# SP.net
KiCad netlist of a schematic drawn in EAGLE
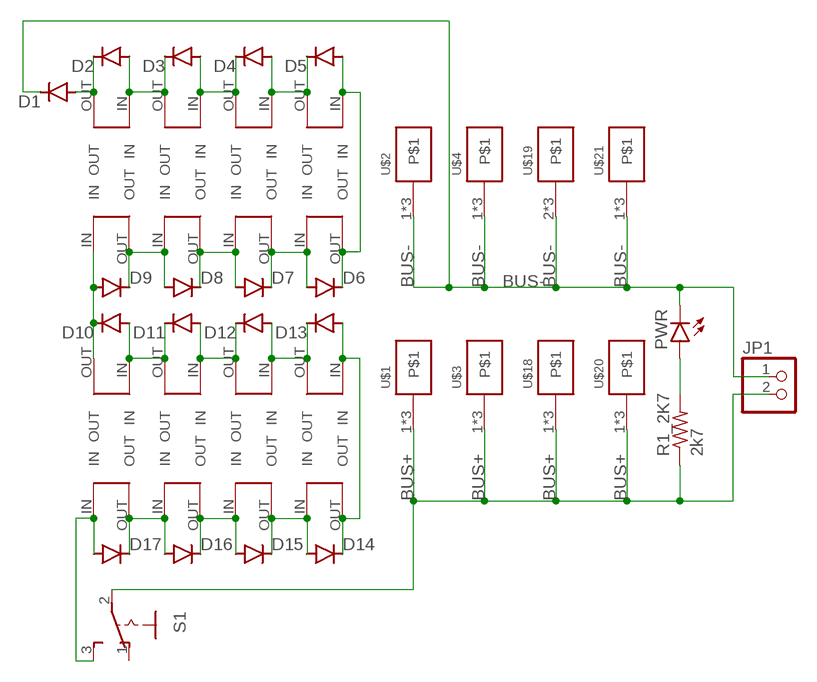
[diagram p0: schematic, sheet 1]

(export (version "E")
  (design (tool "Eeschema 10.0.6"))
  (components
    (comp (ref "D1")
      (value "MBR0520LT")
      (footprint "eagle-import:SOD123")
      (libsource (lib "eagle-import") (part "MBR0520LT"))
    )
    (comp (ref "D2")
      (value "MBR0520LT")
      (footprint "eagle-import:SOD123")
      (libsource (lib "eagle-import") (part "MBR0520LT"))
    )
    (comp (ref "D3")
      (value "MBR0520LT")
      (footprint "eagle-import:SOD123")
      (libsource (lib "eagle-import") (part "MBR0520LT"))
    )
    (comp (ref "D4")
      (value "MBR0520LT")
      (footprint "eagle-import:SOD123")
      (libsource (lib "eagle-import") (part "MBR0520LT"))
    )
    (comp (ref "D5")
      (value "MBR0520LT")
      (footprint "eagle-import:SOD123")
      (libsource (lib "eagle-import") (part "MBR0520LT"))
    )
    (comp (ref "D6")
      (value "MBR0520LT")
      (footprint "eagle-import:SOD123")
      (libsource (lib "eagle-import") (part "MBR0520LT"))
    )
    (comp (ref "D7")
      (value "MBR0520LT")
      (footprint "eagle-import:SOD123")
      (libsource (lib "eagle-import") (part "MBR0520LT"))
    )
    (comp (ref "D8")
      (value "MBR0520LT")
      (footprint "eagle-import:SOD123")
      (libsource (lib "eagle-import") (part "MBR0520LT"))
    )
    (comp (ref "D9")
      (value "MBR0520LT")
      (footprint "eagle-import:SOD123")
      (libsource (lib "eagle-import") (part "MBR0520LT"))
    )
    (comp (ref "D10")
      (value "MBR0520LT")
      (footprint "eagle-import:SOD123")
      (libsource (lib "eagle-import") (part "MBR0520LT"))
    )
    (comp (ref "D11")
      (value "MBR0520LT")
      (footprint "eagle-import:SOD123")
      (libsource (lib "eagle-import") (part "MBR0520LT"))
    )
    (comp (ref "D12")
      (value "MBR0520LT")
      (footprint "eagle-import:SOD123")
      (libsource (lib "eagle-import") (part "MBR0520LT"))
    )
    (comp (ref "D13")
      (value "MBR0520LT")
      (footprint "eagle-import:SOD123")
      (libsource (lib "eagle-import") (part "MBR0520LT"))
    )
    (comp (ref "D14")
      (value "MBR0520LT")
      (footprint "eagle-import:SOD123")
      (libsource (lib "eagle-import") (part "MBR0520LT"))
    )
    (comp (ref "D15")
      (value "MBR0520LT")
      (footprint "eagle-import:SOD123")
      (libsource (lib "eagle-import") (part "MBR0520LT"))
    )
    (comp (ref "D16")
      (value "MBR0520LT")
      (footprint "eagle-import:SOD123")
      (libsource (lib "eagle-import") (part "MBR0520LT"))
    )
    (comp (ref "D17")
      (value "MBR0520LT")
      (footprint "eagle-import:SOD123")
      (libsource (lib "eagle-import") (part "MBR0520LT"))
    )
    (comp (ref "JP1")
      (value "PINHD-1X2")
      (footprint "eagle-import:1X02")
      (libsource (lib "eagle-import") (part "PINHD-1X2"))
    )
    (comp (ref "PWR")
      (value "LEDCHIPLED_0603")
      (footprint "eagle-import:CHIPLED_0603")
      (libsource (lib "eagle-import") (part "LEDCHIPLED_0603"))
    )
    (comp (ref "R1_2K7")
      (value "2k7")
      (footprint "eagle-import:R0603")
      (libsource (lib "eagle-import") (part "R-US_R0603"))
    )
    (comp (ref "S1")
      (value "255SB")
      (footprint "eagle-import:255SB")
      (libsource (lib "eagle-import") (part "255SB"))
    )
    (comp (ref "SOL1")
      (value "SOLAR_0")
      (footprint "eagle-import:SOLAR_0")
      (libsource (lib "eagle-import") (part "SOLAR_0"))
    )
    (comp (ref "SOL2")
      (value "SOLAR_0")
      (footprint "eagle-import:SOLAR_0")
      (libsource (lib "eagle-import") (part "SOLAR_0"))
    )
    (comp (ref "SOL3")
      (value "SOLAR_0")
      (footprint "eagle-import:SOLAR_0")
      (libsource (lib "eagle-import") (part "SOLAR_0"))
    )
    (comp (ref "SOL4")
      (value "SOLAR_1")
      (footprint "eagle-import:SOLAR_1")
      (libsource (lib "eagle-import") (part "SOLAR_1"))
    )
    (comp (ref "SOL5")
      (value "SOLAR_0")
      (footprint "eagle-import:SOLAR_0")
      (libsource (lib "eagle-import") (part "SOLAR_0"))
    )
    (comp (ref "SOL6")
      (value "SOLAR_0")
      (footprint "eagle-import:SOLAR_0")
      (libsource (lib "eagle-import") (part "SOLAR_0"))
    )
    (comp (ref "SOL7")
      (value "SOLAR_0")
      (footprint "eagle-import:SOLAR_0")
      (libsource (lib "eagle-import") (part "SOLAR_0"))
    )
    (comp (ref "SOL8")
      (value "SOLAR_1")
      (footprint "eagle-import:SOLAR_1")
      (libsource (lib "eagle-import") (part "SOLAR_1"))
    )
    (comp (ref "SOL9")
      (value "SOLAR_0")
      (footprint "eagle-import:SOLAR_0")
      (libsource (lib "eagle-import") (part "SOLAR_0"))
    )
    (comp (ref "SOL10")
      (value "SOLAR_0")
      (footprint "eagle-import:SOLAR_0")
      (libsource (lib "eagle-import") (part "SOLAR_0"))
    )
    (comp (ref "SOL11")
      (value "SOLAR_0")
      (footprint "eagle-import:SOLAR_0")
      (libsource (lib "eagle-import") (part "SOLAR_0"))
    )
    (comp (ref "SOL12")
      (value "SOLAR_1")
      (footprint "eagle-import:SOLAR_1")
      (libsource (lib "eagle-import") (part "SOLAR_1"))
    )
    (comp (ref "SOL13")
      (value "SOLAR_0")
      (footprint "eagle-import:SOLAR_0")
      (libsource (lib "eagle-import") (part "SOLAR_0"))
    )
    (comp (ref "SOL14")
      (value "SOLAR_0")
      (footprint "eagle-import:SOLAR_0")
      (libsource (lib "eagle-import") (part "SOLAR_0"))
    )
    (comp (ref "SOL15")
      (value "SOLAR_0")
      (footprint "eagle-import:SOLAR_0")
      (libsource (lib "eagle-import") (part "SOLAR_0"))
    )
    (comp (ref "SOL16")
      (value "SOLAR_1")
      (footprint "eagle-import:SOLAR_1")
      (libsource (lib "eagle-import") (part "SOLAR_1"))
    )
    (comp (ref "U$1")
      (value "KCONNECT3")
      (footprint "eagle-import:KCONNECT-3")
      (libsource (lib "eagle-import") (part "KCONNECT3"))
    )
    (comp (ref "U$2")
      (value "KCONNECT3")
      (footprint "eagle-import:KCONNECT-3")
      (libsource (lib "eagle-import") (part "KCONNECT3"))
    )
    (comp (ref "U$3")
      (value "KCONNECT4")
      (footprint "eagle-import:KCONNECT-4")
      (libsource (lib "eagle-import") (part "KCONNECT4"))
    )
    (comp (ref "U$4")
      (value "KCONNECT4")
      (footprint "eagle-import:KCONNECT-4")
      (libsource (lib "eagle-import") (part "KCONNECT4"))
    )
    (comp (ref "U$18")
      (value "KCONNECT4")
      (footprint "eagle-import:KCONNECT-4")
      (libsource (lib "eagle-import") (part "KCONNECT4"))
    )
    (comp (ref "U$19")
      (value "KCONNECT1")
      (footprint "eagle-import:KCONNECT-1")
      (libsource (lib "eagle-import") (part "KCONNECT1"))
    )
    (comp (ref "U$20")
      (value "KCONNECT3")
      (footprint "eagle-import:KCONNECT-3")
      (libsource (lib "eagle-import") (part "KCONNECT3"))
    )
    (comp (ref "U$21")
      (value "KCONNECT3")
      (footprint "eagle-import:KCONNECT-3")
      (libsource (lib "eagle-import") (part "KCONNECT3"))
    )
  )
  (nets
    (net (code "1") (name "/BUS+") (class "Default")
      (node (ref "JP1") (pin "2") (pinfunction "2_2") (pintype "passive"))
      (node (ref "R1_2K7") (pin "1") (pinfunction "1_1") (pintype "passive"))
      (node (ref "S1") (pin "2") (pinfunction "P_2") (pintype "passive"))
      (node (ref "U$1") (pin "1") (pinfunction "P$1_1") (pintype "bidirectional"))
      (node (ref "U$1") (pin "2") (pinfunction "P$1_2") (pintype "bidirectional"))
      (node (ref "U$1") (pin "4") (pinfunction "P$1_4") (pintype "bidirectional"))
      (node (ref "U$18") (pin "1") (pinfunction "P$1_1") (pintype "bidirectional"))
      (node (ref "U$18") (pin "2") (pinfunction "P$1_2") (pintype "bidirectional"))
      (node (ref "U$18") (pin "3") (pinfunction "P$1_3") (pintype "bidirectional"))
      (node (ref "U$20") (pin "1") (pinfunction "P$1_1") (pintype "bidirectional"))
      (node (ref "U$20") (pin "2") (pinfunction "P$1_2") (pintype "bidirectional"))
      (node (ref "U$20") (pin "4") (pinfunction "P$1_4") (pintype "bidirectional"))
      (node (ref "U$3") (pin "1") (pinfunction "P$1_1") (pintype "bidirectional"))
      (node (ref "U$3") (pin "2") (pinfunction "P$1_2") (pintype "bidirectional"))
      (node (ref "U$3") (pin "3") (pinfunction "P$1_3") (pintype "bidirectional"))
    )
    (net (code "2") (name "/BUS-") (class "Default")
      (node (ref "D1") (pin "C") (pinfunction "C_C") (pintype "passive"))
      (node (ref "JP1") (pin "1") (pinfunction "1_1") (pintype "passive"))
      (node (ref "PWR") (pin "C") (pinfunction "C_C") (pintype "passive"))
      (node (ref "U$19") (pin "2") (pinfunction "P$1_2") (pintype "bidirectional"))
      (node (ref "U$19") (pin "3") (pinfunction "P$1_3") (pintype "bidirectional"))
      (node (ref "U$19") (pin "4") (pinfunction "P$1_4") (pintype "bidirectional"))
      (node (ref "U$2") (pin "1") (pinfunction "P$1_1") (pintype "bidirectional"))
      (node (ref "U$2") (pin "2") (pinfunction "P$1_2") (pintype "bidirectional"))
      (node (ref "U$2") (pin "4") (pinfunction "P$1_4") (pintype "bidirectional"))
      (node (ref "U$21") (pin "1") (pinfunction "P$1_1") (pintype "bidirectional"))
      (node (ref "U$21") (pin "2") (pinfunction "P$1_2") (pintype "bidirectional"))
      (node (ref "U$21") (pin "4") (pinfunction "P$1_4") (pintype "bidirectional"))
      (node (ref "U$4") (pin "1") (pinfunction "P$1_1") (pintype "bidirectional"))
      (node (ref "U$4") (pin "2") (pinfunction "P$1_2") (pintype "bidirectional"))
      (node (ref "U$4") (pin "3") (pinfunction "P$1_3") (pintype "bidirectional"))
    )
    (net (code "3") (name "Net-(D1-PadA)") (class "Default")
      (node (ref "D1") (pin "A") (pinfunction "A_A") (pintype "passive"))
      (node (ref "D2") (pin "C") (pinfunction "C_C") (pintype "passive"))
      (node (ref "SOL16") (pin "OUT") (pinfunction "OUT_OUT") (pintype "bidirectional"))
    )
    (net (code "4") (name "Net-(D2-PadA)") (class "Default")
      (node (ref "D2") (pin "A") (pinfunction "A_A") (pintype "passive"))
      (node (ref "D3") (pin "C") (pinfunction "C_C") (pintype "passive"))
      (node (ref "SOL15") (pin "OUT") (pinfunction "OUT_OUT") (pintype "bidirectional"))
      (node (ref "SOL16") (pin "IN") (pinfunction "IN_IN") (pintype "bidirectional"))
    )
    (net (code "5") (name "Net-(D3-PadA)") (class "Default")
      (node (ref "D3") (pin "A") (pinfunction "A_A") (pintype "passive"))
      (node (ref "D4") (pin "C") (pinfunction "C_C") (pintype "passive"))
      (node (ref "SOL14") (pin "OUT") (pinfunction "OUT_OUT") (pintype "bidirectional"))
      (node (ref "SOL15") (pin "IN") (pinfunction "IN_IN") (pintype "bidirectional"))
    )
    (net (code "6") (name "Net-(D4-PadA)") (class "Default")
      (node (ref "D4") (pin "A") (pinfunction "A_A") (pintype "passive"))
      (node (ref "D5") (pin "C") (pinfunction "C_C") (pintype "passive"))
      (node (ref "SOL13") (pin "OUT") (pinfunction "OUT_OUT") (pintype "bidirectional"))
      (node (ref "SOL14") (pin "IN") (pinfunction "IN_IN") (pintype "bidirectional"))
    )
    (net (code "7") (name "Net-(D5-PadA)") (class "Default")
      (node (ref "D5") (pin "A") (pinfunction "A_A") (pintype "passive"))
      (node (ref "D6") (pin "C") (pinfunction "C_C") (pintype "passive"))
      (node (ref "SOL12") (pin "OUT") (pinfunction "OUT_OUT") (pintype "bidirectional"))
      (node (ref "SOL13") (pin "IN") (pinfunction "IN_IN") (pintype "bidirectional"))
    )
    (net (code "8") (name "Net-(D6-PadA)") (class "Default")
      (node (ref "D6") (pin "A") (pinfunction "A_A") (pintype "passive"))
      (node (ref "D7") (pin "C") (pinfunction "C_C") (pintype "passive"))
      (node (ref "SOL11") (pin "OUT") (pinfunction "OUT_OUT") (pintype "bidirectional"))
      (node (ref "SOL12") (pin "IN") (pinfunction "IN_IN") (pintype "bidirectional"))
    )
    (net (code "9") (name "Net-(D7-PadA)") (class "Default")
      (node (ref "D7") (pin "A") (pinfunction "A_A") (pintype "passive"))
      (node (ref "D8") (pin "C") (pinfunction "C_C") (pintype "passive"))
      (node (ref "SOL10") (pin "OUT") (pinfunction "OUT_OUT") (pintype "bidirectional"))
      (node (ref "SOL11") (pin "IN") (pinfunction "IN_IN") (pintype "bidirectional"))
    )
    (net (code "10") (name "Net-(D8-PadA)") (class "Default")
      (node (ref "D8") (pin "A") (pinfunction "A_A") (pintype "passive"))
      (node (ref "D9") (pin "C") (pinfunction "C_C") (pintype "passive"))
      (node (ref "SOL10") (pin "IN") (pinfunction "IN_IN") (pintype "bidirectional"))
      (node (ref "SOL9") (pin "OUT") (pinfunction "OUT_OUT") (pintype "bidirectional"))
    )
    (net (code "11") (name "Net-(D10-PadA)") (class "Default")
      (node (ref "D10") (pin "A") (pinfunction "A_A") (pintype "passive"))
      (node (ref "D11") (pin "C") (pinfunction "C_C") (pintype "passive"))
      (node (ref "SOL7") (pin "OUT") (pinfunction "OUT_OUT") (pintype "bidirectional"))
      (node (ref "SOL8") (pin "IN") (pinfunction "IN_IN") (pintype "bidirectional"))
    )
    (net (code "12") (name "Net-(D10-PadC)") (class "Default")
      (node (ref "D10") (pin "C") (pinfunction "C_C") (pintype "passive"))
      (node (ref "D9") (pin "A") (pinfunction "A_A") (pintype "passive"))
      (node (ref "SOL8") (pin "OUT") (pinfunction "OUT_OUT") (pintype "bidirectional"))
      (node (ref "SOL9") (pin "IN") (pinfunction "IN_IN") (pintype "bidirectional"))
    )
    (net (code "13") (name "Net-(D11-PadA)") (class "Default")
      (node (ref "D11") (pin "A") (pinfunction "A_A") (pintype "passive"))
      (node (ref "D12") (pin "C") (pinfunction "C_C") (pintype "passive"))
      (node (ref "SOL6") (pin "OUT") (pinfunction "OUT_OUT") (pintype "bidirectional"))
      (node (ref "SOL7") (pin "IN") (pinfunction "IN_IN") (pintype "bidirectional"))
    )
    (net (code "14") (name "Net-(D12-PadA)") (class "Default")
      (node (ref "D12") (pin "A") (pinfunction "A_A") (pintype "passive"))
      (node (ref "D13") (pin "C") (pinfunction "C_C") (pintype "passive"))
      (node (ref "SOL5") (pin "OUT") (pinfunction "OUT_OUT") (pintype "bidirectional"))
      (node (ref "SOL6") (pin "IN") (pinfunction "IN_IN") (pintype "bidirectional"))
    )
    (net (code "15") (name "Net-(D13-PadA)") (class "Default")
      (node (ref "D13") (pin "A") (pinfunction "A_A") (pintype "passive"))
      (node (ref "D14") (pin "C") (pinfunction "C_C") (pintype "passive"))
      (node (ref "SOL4") (pin "OUT") (pinfunction "OUT_OUT") (pintype "bidirectional"))
      (node (ref "SOL5") (pin "IN") (pinfunction "IN_IN") (pintype "bidirectional"))
    )
    (net (code "16") (name "Net-(D14-PadA)") (class "Default")
      (node (ref "D14") (pin "A") (pinfunction "A_A") (pintype "passive"))
      (node (ref "D15") (pin "C") (pinfunction "C_C") (pintype "passive"))
      (node (ref "SOL3") (pin "OUT") (pinfunction "OUT_OUT") (pintype "bidirectional"))
      (node (ref "SOL4") (pin "IN") (pinfunction "IN_IN") (pintype "bidirectional"))
    )
    (net (code "17") (name "Net-(D15-PadA)") (class "Default")
      (node (ref "D15") (pin "A") (pinfunction "A_A") (pintype "passive"))
      (node (ref "D16") (pin "C") (pinfunction "C_C") (pintype "passive"))
      (node (ref "SOL2") (pin "OUT") (pinfunction "OUT_OUT") (pintype "bidirectional"))
      (node (ref "SOL3") (pin "IN") (pinfunction "IN_IN") (pintype "bidirectional"))
    )
    (net (code "18") (name "Net-(D16-PadA)") (class "Default")
      (node (ref "D16") (pin "A") (pinfunction "A_A") (pintype "passive"))
      (node (ref "D17") (pin "C") (pinfunction "C_C") (pintype "passive"))
      (node (ref "SOL1") (pin "OUT") (pinfunction "OUT_OUT") (pintype "bidirectional"))
      (node (ref "SOL2") (pin "IN") (pinfunction "IN_IN") (pintype "bidirectional"))
    )
    (net (code "19") (name "Net-(PWR-PadA)") (class "Default")
      (node (ref "PWR") (pin "A") (pinfunction "A_A") (pintype "passive"))
      (node (ref "R1_2K7") (pin "2") (pinfunction "2_2") (pintype "passive"))
    )
    (net (code "20") (name "Net-(S1-S)") (class "Default")
      (node (ref "D17") (pin "A") (pinfunction "A_A") (pintype "passive"))
      (node (ref "S1") (pin "3") (pinfunction "S_3") (pintype "passive"))
      (node (ref "SOL1") (pin "IN") (pinfunction "IN_IN") (pintype "bidirectional"))
    )
    (net (code "21") (name "unconnected-(S1-O-Pad1)") (class "Default")
      (node (ref "S1") (pin "1") (pinfunction "O_1") (pintype "passive"))
    )
  )
)
